# design.net
KiCad netlist of a schematic drawn in Altium Designer
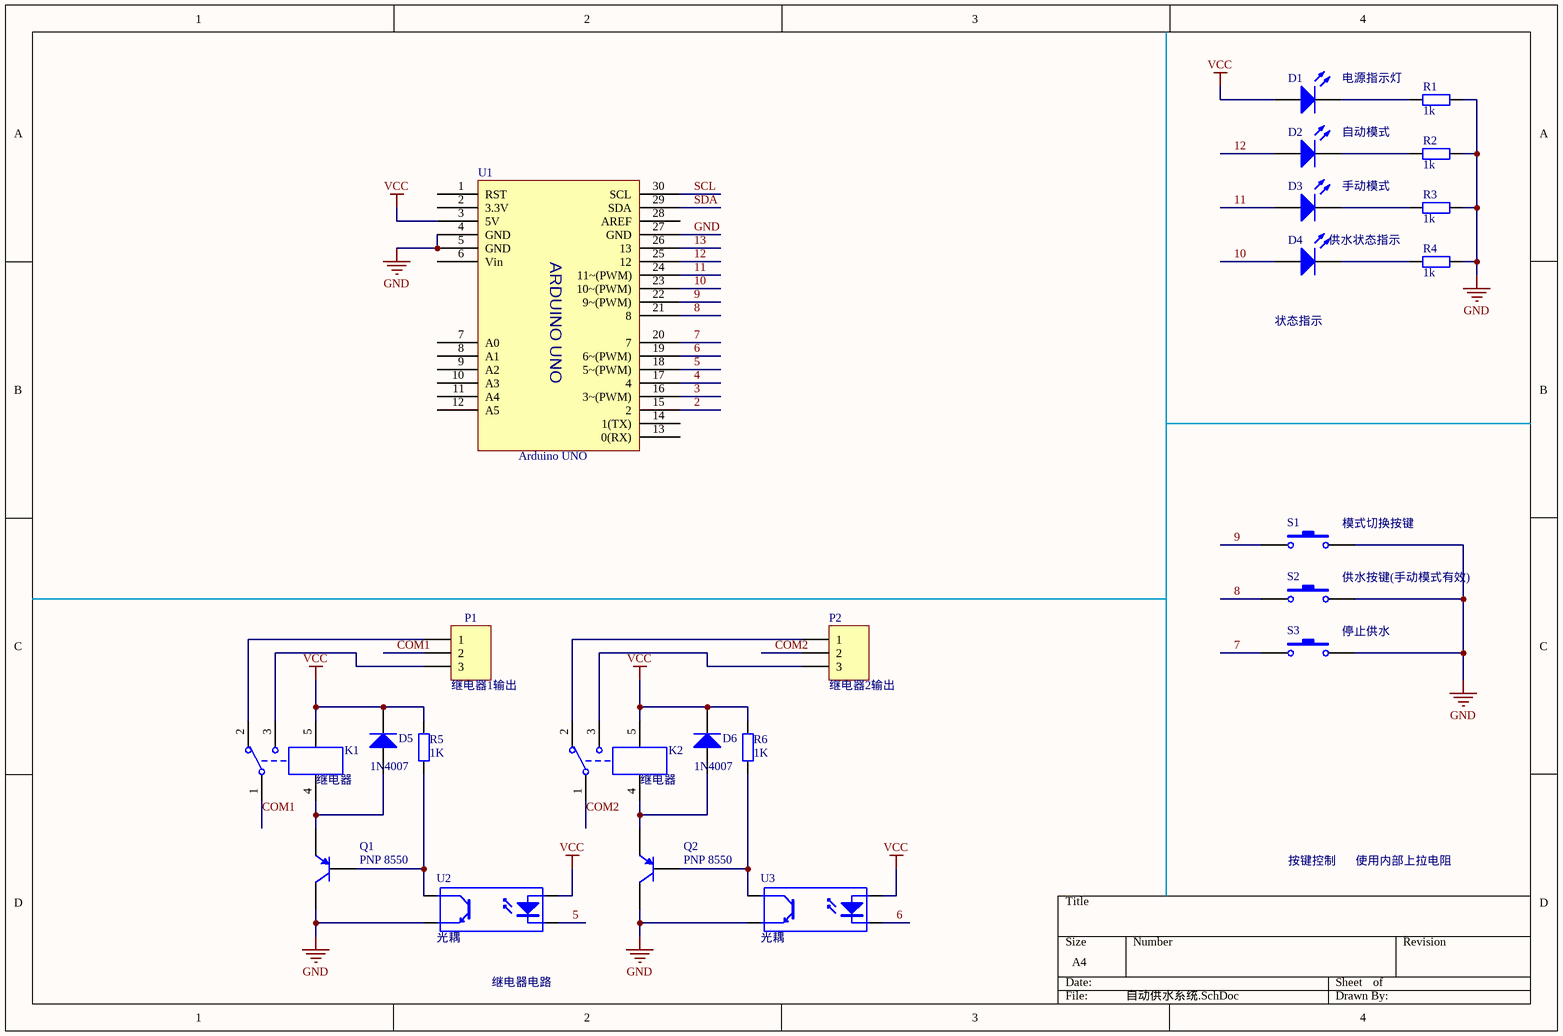
[diagram p0: 自动供水系统.SchDoc]

(export (version "E")
  (design (tool "Eeschema 10.0.6"))
  (components
    (comp (ref "D1")
      (value "LED0")
      (footprint "LED-0")
      (description "Typical INFRARED GaAs LED")
      (fields (field (name "PUBLISHER") "Altium Limited"))
      (libsource (lib "Miscellaneous Devices") (part "LED0"))
    )
    (comp (ref "D2")
      (value "LED0")
      (footprint "LED-0")
      (description "Typical INFRARED GaAs LED")
      (fields (field (name "PUBLISHER") "Altium Limited"))
      (libsource (lib "Miscellaneous Devices") (part "LED0"))
    )
    (comp (ref "D3")
      (value "LED0")
      (footprint "LED-0")
      (description "Typical INFRARED GaAs LED")
      (fields (field (name "PUBLISHER") "Altium Limited"))
      (libsource (lib "Miscellaneous Devices") (part "LED0"))
    )
    (comp (ref "D4")
      (value "LED0")
      (footprint "LED-0")
      (description "Typical INFRARED GaAs LED")
      (fields (field (name "PUBLISHER") "Altium Limited"))
      (libsource (lib "Miscellaneous Devices") (part "LED0"))
    )
    (comp (ref "D5")
      (value "1N4007")
      (footprint "AXIAL-0.4")
      (description "Default Diode")
      (fields (field (name "PUBLISHER") "Altium Limited"))
      (libsource (lib "Miscellaneous Devices") (part "Diode"))
    )
    (comp (ref "D6")
      (value "1N4007")
      (footprint "AXIAL-0.4")
      (description "Default Diode")
      (fields (field (name "PUBLISHER") "Altium Limited"))
      (libsource (lib "Miscellaneous Devices") (part "Diode"))
    )
    (comp (ref "K1") (value "继电器") (footprint "继电器") (libsource (lib "空气检测与净化系统") (part "继电器")))
    (comp (ref "K2") (value "继电器") (footprint "继电器") (libsource (lib "空气检测与净化系统") (part "继电器")))
    (comp (ref "P1")
      (value "继电器1输出")
      (footprint "接线端子")
      (description "Header, 3-Pin")
      (fields (field (name "PUBLISHER") "Altium Limited"))
      (libsource (lib "Miscellaneous Connectors") (part "Header 3"))
    )
    (comp (ref "P2")
      (value "继电器2输出")
      (footprint "接线端子")
      (description "Header, 3-Pin")
      (fields (field (name "PUBLISHER") "Altium Limited"))
      (libsource (lib "Miscellaneous Connectors") (part "Header 3"))
    )
    (comp (ref "Q1")
      (value "PNP 8550")
      (footprint "三极管")
      (description "PNP General Purpose Amplifier")
      (fields (field (name "PUBLISHER") "Altium Limited"))
      (libsource (lib "Miscellaneous Devices") (part "2N3906"))
    )
    (comp (ref "Q2")
      (value "PNP 8550")
      (footprint "三极管")
      (description "PNP General Purpose Amplifier")
      (fields (field (name "PUBLISHER") "Altium Limited"))
      (libsource (lib "Miscellaneous Devices") (part "2N3906"))
    )
    (comp (ref "R1")
      (value "1k")
      (footprint "AXIAL-0.4")
      (description "Resistor")
      (fields (field (name "Comment") "Res2") (field (name "PUBLISHER") "Altium Limited"))
      (libsource (lib "Miscellaneous Devices") (part "Res2"))
    )
    (comp (ref "R2")
      (value "1k")
      (footprint "AXIAL-0.4")
      (description "Resistor")
      (fields (field (name "Comment") "Res2") (field (name "PUBLISHER") "Altium Limited"))
      (libsource (lib "Miscellaneous Devices") (part "Res2"))
    )
    (comp (ref "R3")
      (value "1k")
      (footprint "AXIAL-0.4")
      (description "Resistor")
      (fields (field (name "Comment") "Res2") (field (name "PUBLISHER") "Altium Limited"))
      (libsource (lib "Miscellaneous Devices") (part "Res2"))
    )
    (comp (ref "R4")
      (value "1k")
      (footprint "AXIAL-0.4")
      (description "Resistor")
      (fields (field (name "Comment") "Res2") (field (name "PUBLISHER") "Altium Limited"))
      (libsource (lib "Miscellaneous Devices") (part "Res2"))
    )
    (comp (ref "R5")
      (value "1K")
      (footprint "AXIAL-0.4")
      (description "Resistor")
      (fields (field (name "Comment") "Res2") (field (name "PUBLISHER") "Altium Limited"))
      (libsource (lib "") (part "Res2_1"))
    )
    (comp (ref "R6")
      (value "1K")
      (footprint "AXIAL-0.4")
      (description "Resistor")
      (fields (field (name "Comment") "Res2") (field (name "PUBLISHER") "Altium Limited"))
      (libsource (lib "") (part "Res2_1"))
    )
    (comp (ref "S1")
      (value "SW-PB")
      (footprint "SPST-2")
      (description "Switch")
      (fields (field (name "PUBLISHER") "Altium Limited"))
      (libsource (lib "Miscellaneous Devices") (part "SW-PB"))
    )
    (comp (ref "S2")
      (value "SW-PB")
      (footprint "SPST-2")
      (description "Switch")
      (fields (field (name "PUBLISHER") "Altium Limited"))
      (libsource (lib "Miscellaneous Devices") (part "SW-PB"))
    )
    (comp (ref "S3")
      (value "SW-PB")
      (footprint "SPST-2")
      (description "Switch")
      (fields (field (name "PUBLISHER") "Altium Limited"))
      (libsource (lib "Miscellaneous Devices") (part "SW-PB"))
    )
    (comp (ref "U1")
      (value "Arduino UNO")
      (footprint "Arduino UNO")
      (libsource (lib "自动供水系统") (part "Arduino UNO"))
    )
    (comp (ref "U2")
      (value "光耦")
      (footprint "DIP-4")
      (description "4-Pin Phototransistor Optocoupler")
      (fields (field (name "PUBLISHER") "Altium Limited"))
      (libsource (lib "Miscellaneous Devices") (part "Optoisolator1"))
    )
    (comp (ref "U3")
      (value "光耦")
      (footprint "DIP-4")
      (description "4-Pin Phototransistor Optocoupler")
      (fields (field (name "PUBLISHER") "Altium Limited"))
      (libsource (lib "Miscellaneous Devices") (part "Optoisolator1"))
    )
  )
  (nets
    (net (code "1") (name "/2") (class "Default")
      (node (ref "U1") (pin "15") (pinfunction "2_15") (pintype "passive"))
    )
    (net (code "2") (name "/3") (class "Default")
      (node (ref "U1") (pin "16") (pinfunction "3~(PWM)_16") (pintype "passive"))
    )
    (net (code "3") (name "/4") (class "Default")
      (node (ref "U1") (pin "17") (pinfunction "4_17") (pintype "passive"))
    )
    (net (code "4") (name "/5") (class "Default")
      (node (ref "U1") (pin "18") (pinfunction "5~(PWM)_18") (pintype "passive"))
      (node (ref "U2") (pin "2") (pinfunction "K_2") (pintype "passive"))
    )
    (net (code "5") (name "/6") (class "Default")
      (node (ref "U1") (pin "19") (pinfunction "6~(PWM)_19") (pintype "passive"))
      (node (ref "U3") (pin "2") (pinfunction "K_2") (pintype "passive"))
    )
    (net (code "6") (name "/7") (class "Default")
      (node (ref "S3") (pin "1") (pinfunction "1_1") (pintype "passive"))
      (node (ref "U1") (pin "20") (pinfunction "7_20") (pintype "passive"))
    )
    (net (code "7") (name "/8") (class "Default")
      (node (ref "S2") (pin "1") (pinfunction "1_1") (pintype "passive"))
      (node (ref "U1") (pin "21") (pinfunction "8_21") (pintype "passive"))
    )
    (net (code "8") (name "/9") (class "Default")
      (node (ref "S1") (pin "1") (pinfunction "1_1") (pintype "passive"))
      (node (ref "U1") (pin "22") (pinfunction "9~(PWM)_22") (pintype "passive"))
    )
    (net (code "9") (name "/10") (class "Default")
      (node (ref "D4") (pin "1") (pinfunction "A_1") (pintype "passive"))
      (node (ref "U1") (pin "23") (pinfunction "10~(PWM)_23") (pintype "passive"))
    )
    (net (code "10") (name "/11") (class "Default")
      (node (ref "D3") (pin "1") (pinfunction "A_1") (pintype "passive"))
      (node (ref "U1") (pin "24") (pinfunction "11~(PWM)_24") (pintype "passive"))
    )
    (net (code "11") (name "/12") (class "Default")
      (node (ref "D2") (pin "1") (pinfunction "A_1") (pintype "passive"))
      (node (ref "U1") (pin "25") (pinfunction "12_25") (pintype "passive"))
    )
    (net (code "12") (name "/13") (class "Default")
      (node (ref "U1") (pin "26") (pinfunction "13_26") (pintype "passive"))
    )
    (net (code "13") (name "/COM1") (class "Default")
      (node (ref "K1") (pin "1") (pinfunction "1_1") (pintype "passive"))
      (node (ref "P1") (pin "2") (pinfunction "2_2") (pintype "passive"))
    )
    (net (code "14") (name "/COM2") (class "Default")
      (node (ref "K2") (pin "1") (pinfunction "1_1") (pintype "passive"))
      (node (ref "P2") (pin "2") (pinfunction "2_2") (pintype "passive"))
    )
    (net (code "15") (name "/SCL") (class "Default")
      (node (ref "U1") (pin "30") (pinfunction "SCL_30") (pintype "passive"))
    )
    (net (code "16") (name "/SDA") (class "Default")
      (node (ref "U1") (pin "29") (pinfunction "SDA_29") (pintype "passive"))
    )
    (net (code "17") (name "GND") (class "Default")
      (node (ref "Q1") (pin "3") (pinfunction "C_3") (pintype "passive"))
      (node (ref "Q2") (pin "3") (pinfunction "C_3") (pintype "passive"))
      (node (ref "R1") (pin "2") (pinfunction "2_2") (pintype "passive"))
      (node (ref "R2") (pin "2") (pinfunction "2_2") (pintype "passive"))
      (node (ref "R3") (pin "2") (pinfunction "2_2") (pintype "passive"))
      (node (ref "R4") (pin "2") (pinfunction "2_2") (pintype "passive"))
      (node (ref "S1") (pin "2") (pinfunction "2_2") (pintype "passive"))
      (node (ref "S2") (pin "2") (pinfunction "2_2") (pintype "passive"))
      (node (ref "S3") (pin "2") (pinfunction "2_2") (pintype "passive"))
      (node (ref "U1") (pin "27") (pinfunction "GND_27") (pintype "power_in"))
      (node (ref "U1") (pin "4") (pinfunction "GND_4") (pintype "power_in"))
      (node (ref "U1") (pin "5") (pinfunction "GND_5") (pintype "power_in"))
      (node (ref "U2") (pin "3") (pinfunction "E_3") (pintype "passive"))
      (node (ref "U3") (pin "3") (pinfunction "E_3") (pintype "passive"))
    )
    (net (code "18") (name "Net-(D1-K)") (class "Default")
      (node (ref "D1") (pin "2") (pinfunction "K_2") (pintype "passive"))
      (node (ref "R1") (pin "1") (pinfunction "1_1") (pintype "passive"))
    )
    (net (code "19") (name "Net-(D2-K)") (class "Default")
      (node (ref "D2") (pin "2") (pinfunction "K_2") (pintype "passive"))
      (node (ref "R2") (pin "1") (pinfunction "1_1") (pintype "passive"))
    )
    (net (code "20") (name "Net-(D3-K)") (class "Default")
      (node (ref "D3") (pin "2") (pinfunction "K_2") (pintype "passive"))
      (node (ref "R3") (pin "1") (pinfunction "1_1") (pintype "passive"))
    )
    (net (code "21") (name "Net-(D4-K)") (class "Default")
      (node (ref "D4") (pin "2") (pinfunction "K_2") (pintype "passive"))
      (node (ref "R4") (pin "1") (pinfunction "1_1") (pintype "passive"))
    )
    (net (code "22") (name "Net-(D5-A)") (class "Default")
      (node (ref "D5") (pin "1") (pinfunction "A_1") (pintype "passive"))
      (node (ref "K1") (pin "4") (pinfunction "4_4") (pintype "passive"))
      (node (ref "Q1") (pin "1") (pinfunction "E_1") (pintype "passive"))
    )
    (net (code "23") (name "Net-(D6-A)") (class "Default")
      (node (ref "D6") (pin "1") (pinfunction "A_1") (pintype "passive"))
      (node (ref "K2") (pin "4") (pinfunction "4_4") (pintype "passive"))
      (node (ref "Q2") (pin "1") (pinfunction "E_1") (pintype "passive"))
    )
    (net (code "24") (name "Net-(K1-Pad2)") (class "Default")
      (node (ref "K1") (pin "2") (pinfunction "2_2") (pintype "passive"))
      (node (ref "P1") (pin "1") (pinfunction "1_1") (pintype "passive"))
    )
    (net (code "25") (name "Net-(K1-Pad3)") (class "Default")
      (node (ref "K1") (pin "3") (pinfunction "3_3") (pintype "passive"))
      (node (ref "P1") (pin "3") (pinfunction "3_3") (pintype "passive"))
    )
    (net (code "26") (name "Net-(K2-Pad2)") (class "Default")
      (node (ref "K2") (pin "2") (pinfunction "2_2") (pintype "passive"))
      (node (ref "P2") (pin "1") (pinfunction "1_1") (pintype "passive"))
    )
    (net (code "27") (name "Net-(K2-Pad3)") (class "Default")
      (node (ref "K2") (pin "3") (pinfunction "3_3") (pintype "passive"))
      (node (ref "P2") (pin "3") (pinfunction "3_3") (pintype "passive"))
    )
    (net (code "28") (name "Net-(Q1-B)") (class "Default")
      (node (ref "Q1") (pin "2") (pinfunction "B_2") (pintype "passive"))
      (node (ref "R5") (pin "1") (pinfunction "1_1") (pintype "passive"))
      (node (ref "U2") (pin "4") (pinfunction "C_4") (pintype "passive"))
    )
    (net (code "29") (name "Net-(Q2-B)") (class "Default")
      (node (ref "Q2") (pin "2") (pinfunction "B_2") (pintype "passive"))
      (node (ref "R6") (pin "1") (pinfunction "1_1") (pintype "passive"))
      (node (ref "U3") (pin "4") (pinfunction "C_4") (pintype "passive"))
    )
    (net (code "30") (name "VCC") (class "Default")
      (node (ref "D1") (pin "1") (pinfunction "A_1") (pintype "passive"))
      (node (ref "D5") (pin "2") (pinfunction "K_2") (pintype "passive"))
      (node (ref "D6") (pin "2") (pinfunction "K_2") (pintype "passive"))
      (node (ref "K1") (pin "5") (pinfunction "5_5") (pintype "passive"))
      (node (ref "K2") (pin "5") (pinfunction "5_5") (pintype "passive"))
      (node (ref "R5") (pin "2") (pinfunction "2_2") (pintype "passive"))
      (node (ref "R6") (pin "2") (pinfunction "2_2") (pintype "passive"))
      (node (ref "U1") (pin "3") (pinfunction "5V_3") (pintype "power_in"))
      (node (ref "U2") (pin "1") (pinfunction "A_1") (pintype "passive"))
      (node (ref "U3") (pin "1") (pinfunction "A_1") (pintype "passive"))
    )
    (net (code "31") (name "unconnected-(U1-0(RX)-Pad13)") (class "Default")
      (node (ref "U1") (pin "13") (pinfunction "0(RX)_13") (pintype "passive"))
    )
    (net (code "32") (name "unconnected-(U1-1(TX)-Pad14)") (class "Default")
      (node (ref "U1") (pin "14") (pinfunction "1(TX)_14") (pintype "passive"))
    )
    (net (code "33") (name "unconnected-(U1-3.3V-Pad2)") (class "Default")
      (node (ref "U1") (pin "2") (pinfunction "3.3V_2") (pintype "power_in"))
    )
    (net (code "34") (name "unconnected-(U1-A0-Pad7)") (class "Default")
      (node (ref "U1") (pin "7") (pinfunction "A0_7") (pintype "passive"))
    )
    (net (code "35") (name "unconnected-(U1-A1-Pad8)") (class "Default")
      (node (ref "U1") (pin "8") (pinfunction "A1_8") (pintype "passive"))
    )
    (net (code "36") (name "unconnected-(U1-A2-Pad9)") (class "Default")
      (node (ref "U1") (pin "9") (pinfunction "A2_9") (pintype "passive"))
    )
    (net (code "37") (name "unconnected-(U1-A3-Pad10)") (class "Default")
      (node (ref "U1") (pin "10") (pinfunction "A3_10") (pintype "passive"))
    )
    (net (code "38") (name "unconnected-(U1-A4-Pad11)") (class "Default")
      (node (ref "U1") (pin "11") (pinfunction "A4_11") (pintype "passive"))
    )
    (net (code "39") (name "unconnected-(U1-A5-Pad12)") (class "Default")
      (node (ref "U1") (pin "12") (pinfunction "A5_12") (pintype "passive"))
    )
    (net (code "40") (name "unconnected-(U1-AREF-Pad28)") (class "Default")
      (node (ref "U1") (pin "28") (pinfunction "AREF_28") (pintype "passive"))
    )
    (net (code "41") (name "unconnected-(U1-RST-Pad1)") (class "Default")
      (node (ref "U1") (pin "1") (pinfunction "RST_1") (pintype "passive"))
    )
    (net (code "42") (name "unconnected-(U1-Vin-Pad6)") (class "Default")
      (node (ref "U1") (pin "6") (pinfunction "Vin_6") (pintype "passive"))
    )
  )
)
